# SELE_PROJECT.net
KiCad netlist of a schematic drawn in EAGLE
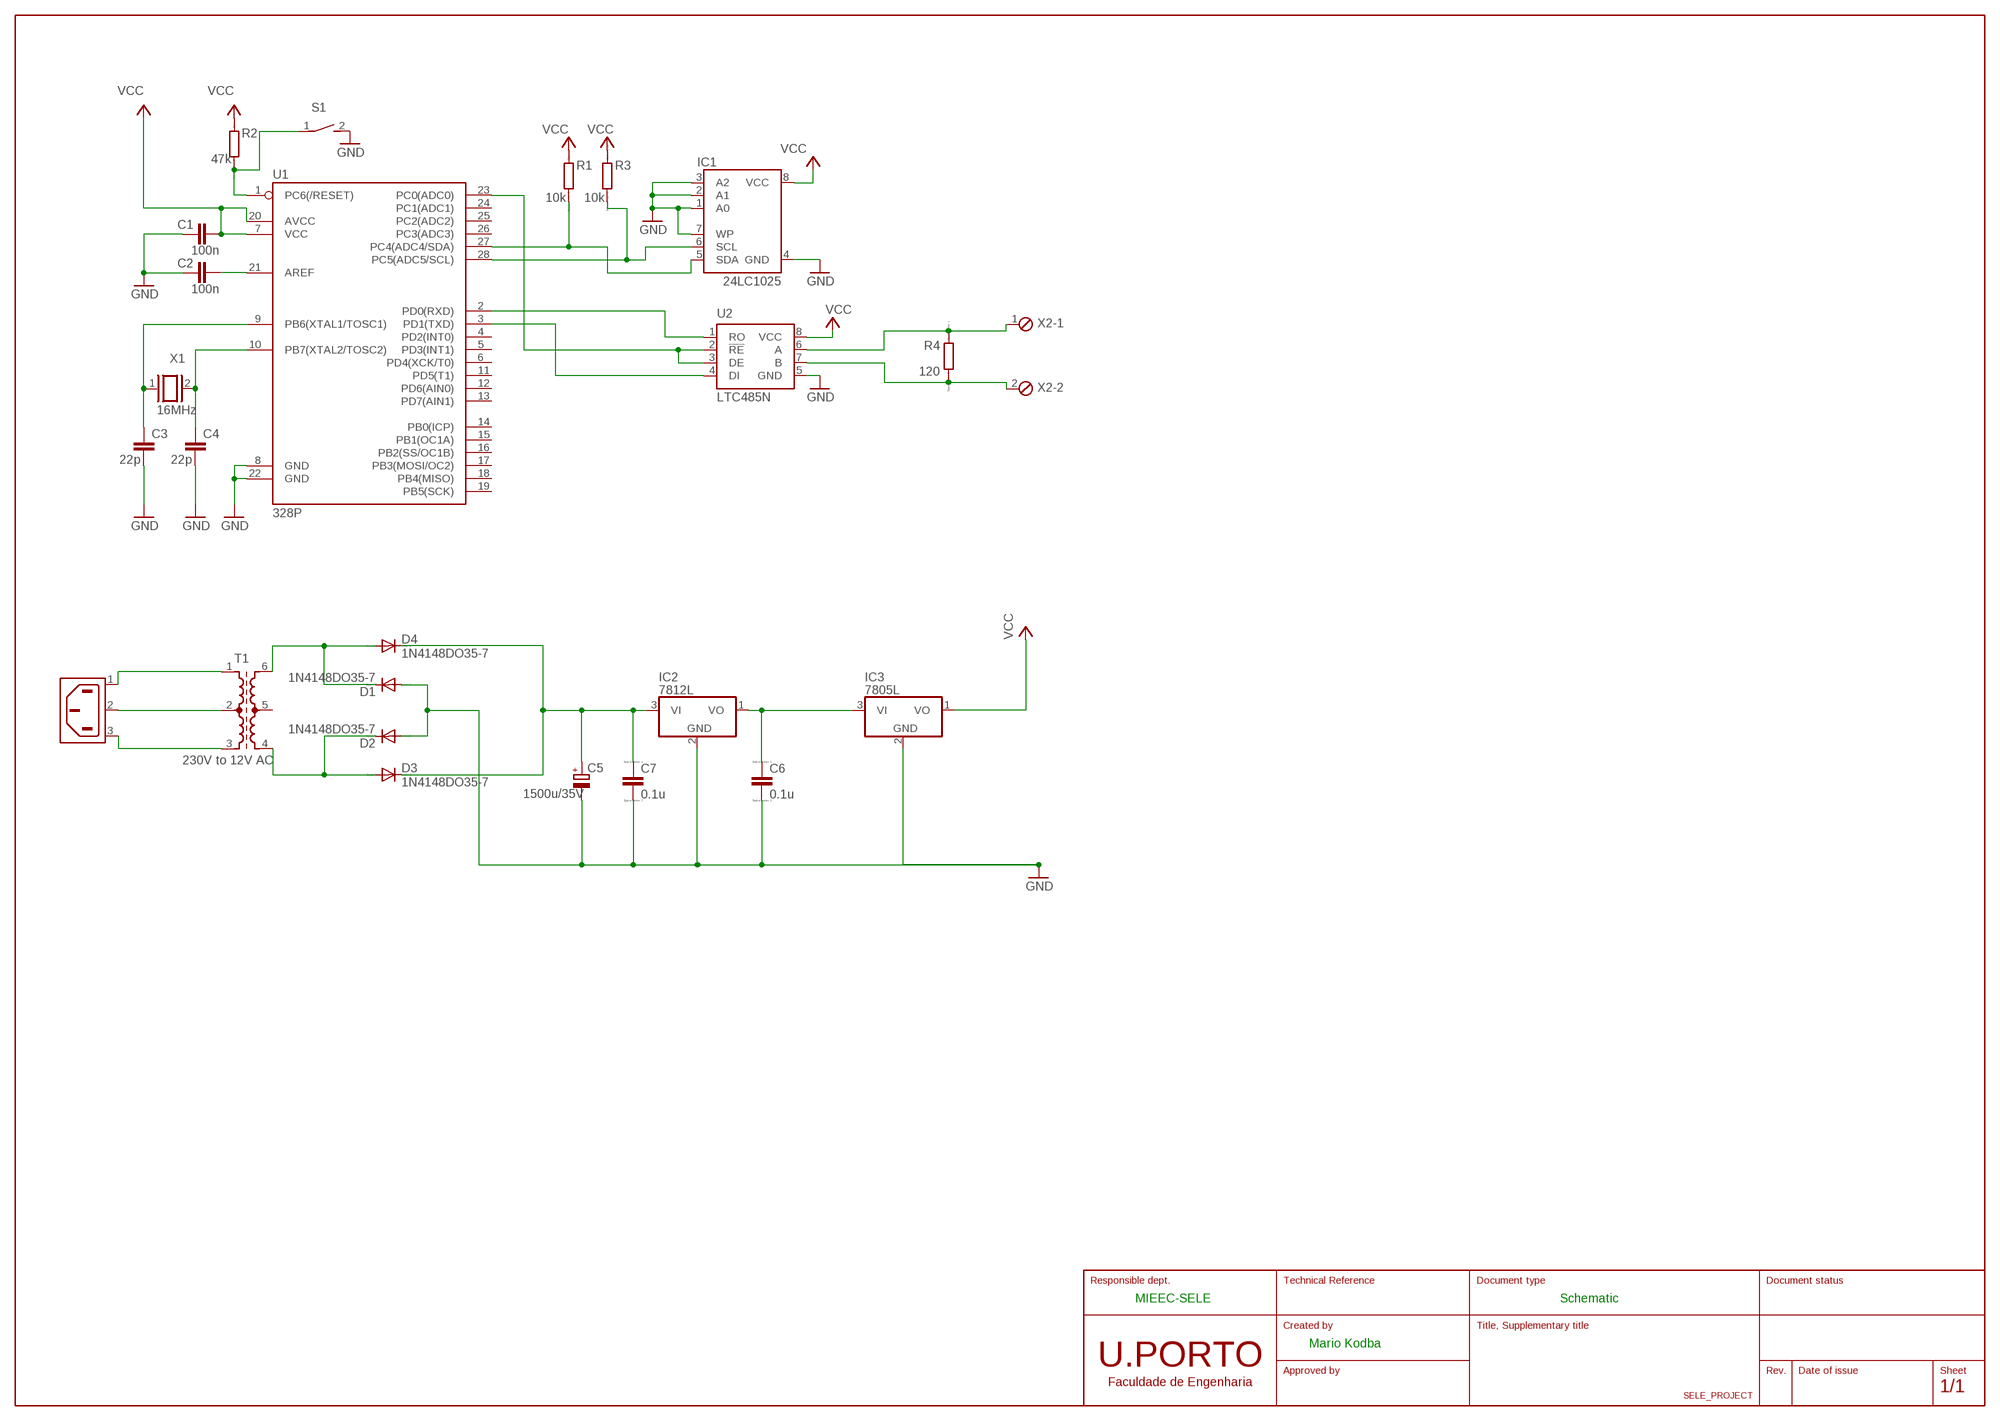
[diagram p0: schematic, sheet 1]

(export (version "E")
  (design (tool "Eeschema 10.0.6"))
  (components
    (comp (ref "C1")
      (value "100n")
      (footprint "eagle-import:C2.5-3")
      (libsource (lib "eagle-import") (part "C2,5-3"))
    )
    (comp (ref "C2")
      (value "100n")
      (footprint "eagle-import:C2.5-3")
      (libsource (lib "eagle-import") (part "C2,5-3"))
    )
    (comp (ref "C3")
      (value "22p")
      (footprint "eagle-import:C2.5-3")
      (libsource (lib "eagle-import") (part "C2,5-3"))
    )
    (comp (ref "C4")
      (value "22p")
      (footprint "eagle-import:C2.5-3")
      (libsource (lib "eagle-import") (part "C2,5-3"))
    )
    (comp (ref "C5")
      (value "1500u/35V")
      (footprint "eagle-import:150CLZ-1010")
      (libsource (lib "eagle-import") (part "CPOL-EU150CLZ-1010"))
    )
    (comp (ref "C6")
      (value "0.1u")
      (footprint "eagle-import:C1210")
      (libsource (lib "eagle-import") (part "CC1210"))
    )
    (comp (ref "C7")
      (value "0.1u")
      (footprint "eagle-import:C1210")
      (libsource (lib "eagle-import") (part "CC1210"))
    )
    (comp (ref "D1")
      (value "1N4148DO35-7")
      (footprint "eagle-import:DO35-7")
      (libsource (lib "eagle-import") (part "1N4148DO35-7"))
    )
    (comp (ref "D2")
      (value "1N4148DO35-7")
      (footprint "eagle-import:DO35-7")
      (libsource (lib "eagle-import") (part "1N4148DO35-7"))
    )
    (comp (ref "D3")
      (value "1N4148DO35-7")
      (footprint "eagle-import:DO35-7")
      (libsource (lib "eagle-import") (part "1N4148DO35-7"))
    )
    (comp (ref "D4")
      (value "1N4148DO35-7")
      (footprint "eagle-import:DO35-7")
      (libsource (lib "eagle-import") (part "1N4148DO35-7"))
    )
    (comp (ref "IC1")
      (value "24LC1025")
      (footprint "eagle-import:DIL08")
      (fields (field (name "MPN") "AT24C1024BW-SH-B"))
      (libsource (lib "eagle-import") (part "AT24CP"))
    )
    (comp (ref "IC2")
      (value "7812L")
      (footprint "eagle-import:TO92")
      (libsource (lib "eagle-import") (part "78L12"))
    )
    (comp (ref "IC3")
      (value "7805L")
      (footprint "eagle-import:TO92")
      (libsource (lib "eagle-import") (part "78L05"))
    )
    (comp (ref "R1")
      (value "10k")
      (footprint "eagle-import:R0805")
      (libsource (lib "eagle-import") (part "R"))
    )
    (comp (ref "R2")
      (value "47k")
      (footprint "eagle-import:R0805")
      (libsource (lib "eagle-import") (part "R"))
    )
    (comp (ref "R3")
      (value "10k")
      (footprint "eagle-import:R0805")
      (libsource (lib "eagle-import") (part "R"))
    )
    (comp (ref "R4")
      (value "120")
      (footprint "eagle-import:R0805")
      (libsource (lib "eagle-import") (part "R"))
    )
    (comp (ref "S1")
      (value "DS01E")
      (footprint "eagle-import:DS-01")
      (libsource (lib "eagle-import") (part "DS01E"))
    )
    (comp (ref "T1")
      (value "230V to 12V AC")
      (footprint "eagle-import:SM-EP7")
      (libsource (lib "eagle-import") (part "SM-EP7"))
    )
    (comp (ref "U1")
      (value "328P")
      (footprint "eagle-import:MICROCONTROLLER_DIP28")
      (libsource (lib "eagle-import") (part "ATMEGA328P-PDIP"))
    )
    (comp (ref "U2")
      (value "LTC485N")
      (footprint "eagle-import:DIL08")
      (libsource (lib "eagle-import") (part "LTC485N"))
    )
    (comp (ref "X1")
      (value "16MHz")
      (footprint "eagle-import:Q")
      (libsource (lib "eagle-import") (part "XTAL"))
    )
    (comp (ref "X2")
      (value "MPT2")
      (footprint "eagle-import:2POL254")
      (libsource (lib "eagle-import") (part "MPT2"))
    )
    (comp (ref "X4")
      (value "6ESRM-P")
      (footprint "eagle-import:6ESRM-P")
      (fields (field (name "MF") "TYCO ELECTRONICS"))
      (libsource (lib "eagle-import") (part "6ESRM-P"))
    )
  )
  (nets
    (net (code "1") (name "GND") (class "Default")
      (node (ref "C1") (pin "1") (pinfunction "1_1") (pintype "passive"))
      (node (ref "C2") (pin "1") (pinfunction "1_1") (pintype "passive"))
      (node (ref "C3") (pin "2") (pinfunction "2_2") (pintype "passive"))
      (node (ref "C4") (pin "2") (pinfunction "2_2") (pintype "passive"))
      (node (ref "C5") (pin "-") (pinfunction "-_-") (pintype "passive"))
      (node (ref "C6") (pin "2") (pinfunction "2_2") (pintype "passive"))
      (node (ref "C7") (pin "2") (pinfunction "2_2") (pintype "passive"))
      (node (ref "D1") (pin "A") (pinfunction "A_A") (pintype "passive"))
      (node (ref "D2") (pin "A") (pinfunction "A_A") (pintype "passive"))
      (node (ref "IC1") (pin "1") (pinfunction "A0_1") (pintype "input"))
      (node (ref "IC1") (pin "2") (pinfunction "A1_2") (pintype "input"))
      (node (ref "IC1") (pin "3") (pinfunction "A2_3") (pintype "input"))
      (node (ref "IC1") (pin "4") (pinfunction "GND_4") (pintype "power_in"))
      (node (ref "IC1") (pin "7") (pinfunction "WP_7") (pintype "input"))
      (node (ref "IC2") (pin "2") (pinfunction "GND_2") (pintype "passive"))
      (node (ref "IC3") (pin "2") (pinfunction "GND_2") (pintype "passive"))
      (node (ref "S1") (pin "2") (pinfunction "2_2") (pintype "passive"))
      (node (ref "U1") (pin "22") (pinfunction "GND_22") (pintype "bidirectional"))
      (node (ref "U1") (pin "8") (pinfunction "GND_8") (pintype "bidirectional"))
      (node (ref "U2") (pin "5") (pinfunction "GND_5") (pintype "input"))
    )
    (net (code "2") (name "Net-(D1-PadC)") (class "Default")
      (node (ref "D1") (pin "C") (pinfunction "C_C") (pintype "passive"))
      (node (ref "D4") (pin "A") (pinfunction "A_A") (pintype "passive"))
      (node (ref "T1") (pin "6") (pinfunction "6_6") (pintype "passive"))
    )
    (net (code "3") (name "Net-(D2-PadC)") (class "Default")
      (node (ref "D2") (pin "C") (pinfunction "C_C") (pintype "passive"))
      (node (ref "D3") (pin "A") (pinfunction "A_A") (pintype "passive"))
      (node (ref "T1") (pin "4") (pinfunction "4_4") (pintype "passive"))
    )
    (net (code "4") (name "Net-(IC1-SCL)") (class "Default")
      (node (ref "IC1") (pin "6") (pinfunction "SCL_6") (pintype "bidirectional"))
      (node (ref "R3") (pin "2") (pinfunction "2_2") (pintype "passive"))
      (node (ref "U1") (pin "28") (pinfunction "PC5(ADC5/SCL)_28") (pintype "bidirectional"))
    )
    (net (code "5") (name "Net-(IC1-SDA)") (class "Default")
      (node (ref "IC1") (pin "5") (pinfunction "SDA_5") (pintype "bidirectional"))
      (node (ref "R1") (pin "2") (pinfunction "2_2") (pintype "passive"))
      (node (ref "U1") (pin "27") (pinfunction "PC4(ADC4/SDA)_27") (pintype "bidirectional"))
    )
    (net (code "6") (name "Net-(IC2-VI)") (class "Default")
      (node (ref "C5") (pin "+") (pinfunction "+_+") (pintype "passive"))
      (node (ref "C7") (pin "1") (pinfunction "1_1") (pintype "passive"))
      (node (ref "D3") (pin "C") (pinfunction "C_C") (pintype "passive"))
      (node (ref "D4") (pin "C") (pinfunction "C_C") (pintype "passive"))
      (node (ref "IC2") (pin "3") (pinfunction "VI_3") (pintype "input"))
    )
    (net (code "7") (name "Net-(IC2-VO)") (class "Default")
      (node (ref "C6") (pin "1") (pinfunction "1_1") (pintype "passive"))
      (node (ref "IC2") (pin "1") (pinfunction "VO_1") (pintype "passive"))
      (node (ref "IC3") (pin "3") (pinfunction "VI_3") (pintype "input"))
    )
    (net (code "8") (name "Net-(U1-AREF)") (class "Default")
      (node (ref "C2") (pin "2") (pinfunction "2_2") (pintype "passive"))
      (node (ref "U1") (pin "21") (pinfunction "AREF_21") (pintype "bidirectional"))
    )
    (net (code "9") (name "Net-(U1-PB6(XTAL1{slash}TOSC1))") (class "Default")
      (node (ref "C3") (pin "1") (pinfunction "1_1") (pintype "passive"))
      (node (ref "U1") (pin "9") (pinfunction "PB6(XTAL1/TOSC1)_9") (pintype "bidirectional"))
      (node (ref "X1") (pin "1") (pinfunction "1_1") (pintype "passive"))
    )
    (net (code "10") (name "Net-(U1-PB7(XTAL2{slash}TOSC2))") (class "Default")
      (node (ref "C4") (pin "1") (pinfunction "1_1") (pintype "passive"))
      (node (ref "U1") (pin "10") (pinfunction "PB7(XTAL2/TOSC2)_10") (pintype "bidirectional"))
      (node (ref "X1") (pin "2") (pinfunction "2_2") (pintype "passive"))
    )
    (net (code "11") (name "Net-(U1-PC0(ADC0))") (class "Default")
      (node (ref "U1") (pin "23") (pinfunction "PC0(ADC0)_23") (pintype "bidirectional"))
      (node (ref "U2") (pin "2") (pinfunction "~{RE}_2") (pintype "input"))
      (node (ref "U2") (pin "3") (pinfunction "DE_3") (pintype "input"))
    )
    (net (code "12") (name "Net-(U1-PC6({slash}RESET))") (class "Default")
      (node (ref "R2") (pin "2") (pinfunction "2_2") (pintype "passive"))
      (node (ref "S1") (pin "1") (pinfunction "1_1") (pintype "passive"))
      (node (ref "U1") (pin "1") (pinfunction "PC6(/RESET)_1") (pintype "bidirectional"))
    )
    (net (code "13") (name "Net-(U1-PD0(RXD))") (class "Default")
      (node (ref "U1") (pin "2") (pinfunction "PD0(RXD)_2") (pintype "bidirectional"))
      (node (ref "U2") (pin "1") (pinfunction "RO_1") (pintype "output"))
    )
    (net (code "14") (name "Net-(U1-PD1(TXD))") (class "Default")
      (node (ref "U1") (pin "3") (pinfunction "PD1(TXD)_3") (pintype "bidirectional"))
      (node (ref "U2") (pin "4") (pinfunction "DI_4") (pintype "input"))
    )
    (net (code "15") (name "Net-(U2-A)") (class "Default")
      (node (ref "R4") (pin "1") (pinfunction "1_1") (pintype "passive"))
      (node (ref "U2") (pin "6") (pinfunction "A_6") (pintype "bidirectional"))
      (node (ref "X2") (pin "1") (pinfunction "1_1") (pintype "passive"))
    )
    (net (code "16") (name "Net-(U2-B)") (class "Default")
      (node (ref "R4") (pin "2") (pinfunction "2_2") (pintype "passive"))
      (node (ref "U2") (pin "7") (pinfunction "B_7") (pintype "bidirectional"))
      (node (ref "X2") (pin "2") (pinfunction "1_2") (pintype "passive"))
    )
    (net (code "17") (name "Net-(X4-AC1)") (class "Default")
      (node (ref "T1") (pin "1") (pinfunction "1_1") (pintype "passive"))
      (node (ref "X4") (pin "1") (pinfunction "AC1_1") (pintype "passive"))
    )
    (net (code "18") (name "Net-(X4-AC2)") (class "Default")
      (node (ref "T1") (pin "3") (pinfunction "3_3") (pintype "passive"))
      (node (ref "X4") (pin "3") (pinfunction "AC2_3") (pintype "passive"))
    )
    (net (code "19") (name "Net-(X4-SH)") (class "Default")
      (node (ref "T1") (pin "2") (pinfunction "2_2") (pintype "passive"))
      (node (ref "X4") (pin "2") (pinfunction "SH_2") (pintype "passive"))
    )
    (net (code "20") (name "VCC") (class "Default")
      (node (ref "C1") (pin "2") (pinfunction "2_2") (pintype "passive"))
      (node (ref "IC1") (pin "8") (pinfunction "VCC_8") (pintype "power_in"))
      (node (ref "IC3") (pin "1") (pinfunction "VO_1") (pintype "passive"))
      (node (ref "R1") (pin "1") (pinfunction "1_1") (pintype "passive"))
      (node (ref "R2") (pin "1") (pinfunction "1_1") (pintype "passive"))
      (node (ref "R3") (pin "1") (pinfunction "1_1") (pintype "passive"))
      (node (ref "U1") (pin "20") (pinfunction "AVCC_20") (pintype "bidirectional"))
      (node (ref "U1") (pin "7") (pinfunction "VCC_7") (pintype "bidirectional"))
      (node (ref "U2") (pin "8") (pinfunction "VCC_8") (pintype "input"))
    )
    (net (code "21") (name "unconnected-(T1-Pad5)") (class "Default")
      (node (ref "T1") (pin "5") (pinfunction "5_5") (pintype "passive"))
    )
    (net (code "22") (name "unconnected-(U1-PB0(ICP)-Pad14)") (class "Default")
      (node (ref "U1") (pin "14") (pinfunction "PB0(ICP)_14") (pintype "bidirectional"))
    )
    (net (code "23") (name "unconnected-(U1-PB1(OC1A)-Pad15)") (class "Default")
      (node (ref "U1") (pin "15") (pinfunction "PB1(OC1A)_15") (pintype "bidirectional"))
    )
    (net (code "24") (name "unconnected-(U1-PB2(SS{slash}OC1B)-Pad16)") (class "Default")
      (node (ref "U1") (pin "16") (pinfunction "PB2(SS/OC1B)_16") (pintype "bidirectional"))
    )
    (net (code "25") (name "unconnected-(U1-PB3(MOSI{slash}OC2)-Pad17)") (class "Default")
      (node (ref "U1") (pin "17") (pinfunction "PB3(MOSI/OC2)_17") (pintype "bidirectional"))
    )
    (net (code "26") (name "unconnected-(U1-PB4(MISO)-Pad18)") (class "Default")
      (node (ref "U1") (pin "18") (pinfunction "PB4(MISO)_18") (pintype "bidirectional"))
    )
    (net (code "27") (name "unconnected-(U1-PB5(SCK)-Pad19)") (class "Default")
      (node (ref "U1") (pin "19") (pinfunction "PB5(SCK)_19") (pintype "bidirectional"))
    )
    (net (code "28") (name "unconnected-(U1-PC1(ADC1)-Pad24)") (class "Default")
      (node (ref "U1") (pin "24") (pinfunction "PC1(ADC1)_24") (pintype "bidirectional"))
    )
    (net (code "29") (name "unconnected-(U1-PC2(ADC2)-Pad25)") (class "Default")
      (node (ref "U1") (pin "25") (pinfunction "PC2(ADC2)_25") (pintype "bidirectional"))
    )
    (net (code "30") (name "unconnected-(U1-PC3(ADC3)-Pad26)") (class "Default")
      (node (ref "U1") (pin "26") (pinfunction "PC3(ADC3)_26") (pintype "bidirectional"))
    )
    (net (code "31") (name "unconnected-(U1-PD2(INT0)-Pad4)") (class "Default")
      (node (ref "U1") (pin "4") (pinfunction "PD2(INT0)_4") (pintype "bidirectional"))
    )
    (net (code "32") (name "unconnected-(U1-PD3(INT1)-Pad5)") (class "Default")
      (node (ref "U1") (pin "5") (pinfunction "PD3(INT1)_5") (pintype "bidirectional"))
    )
    (net (code "33") (name "unconnected-(U1-PD4(XCK{slash}T0)-Pad6)") (class "Default")
      (node (ref "U1") (pin "6") (pinfunction "PD4(XCK/T0)_6") (pintype "bidirectional"))
    )
    (net (code "34") (name "unconnected-(U1-PD5(T1)-Pad11)") (class "Default")
      (node (ref "U1") (pin "11") (pinfunction "PD5(T1)_11") (pintype "bidirectional"))
    )
    (net (code "35") (name "unconnected-(U1-PD6(AIN0)-Pad12)") (class "Default")
      (node (ref "U1") (pin "12") (pinfunction "PD6(AIN0)_12") (pintype "bidirectional"))
    )
    (net (code "36") (name "unconnected-(U1-PD7(AIN1)-Pad13)") (class "Default")
      (node (ref "U1") (pin "13") (pinfunction "PD7(AIN1)_13") (pintype "bidirectional"))
    )
  )
)
